# STM32.net
KiCad netlist of a schematic drawn in Altium Designer
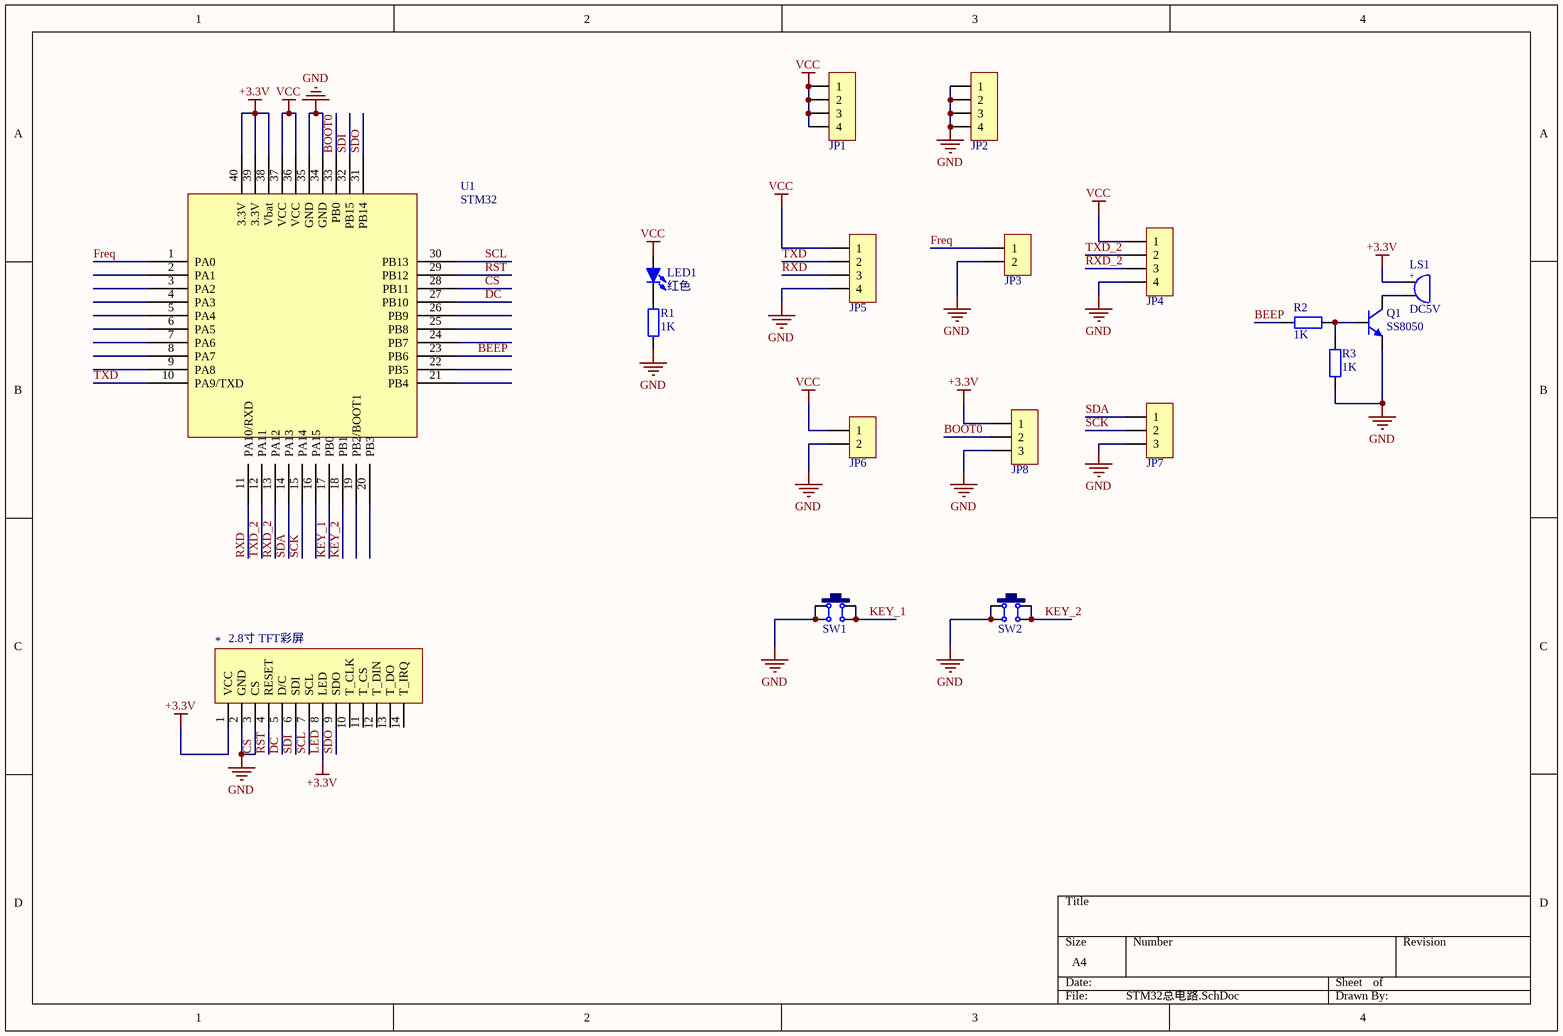
[diagram p0: STM32总电路.SchDoc]

(export (version "E")
  (design (tool "Eeschema 10.0.6"))
  (components
    (comp (ref "*")
      (value "2.8寸 TFT彩屏")
      (footprint "2.8寸TFT屏幕")
      (libsource (lib "altium-import") (part "root_0_2.8寸 TFT彩屏_"))
    )
    (comp (ref "JP1")
      (value "HDR-1X4")
      (footprint "HDR2.54-LI-4P")
      (description "4P接插件")
      (fields (field (name "版权归属") "源创客"))
      (libsource (lib "4.5   - 接插件-脚距2.54") (part "Header 4"))
    )
    (comp (ref "JP2")
      (value "HDR-1X4")
      (footprint "HDR2.54-LI-4P")
      (description "4P接插件")
      (fields (field (name "版权归属") "源创客"))
      (libsource (lib "4.5   - 接插件-脚距2.54") (part "Header 4"))
    )
    (comp (ref "JP3")
      (value "HDR-1X2")
      (footprint "XH2.54-LI-2P")
      (description "2P接插件")
      (fields (field (name "版权归属") "源创客"))
      (libsource (lib "4.5   - 接插件-脚距2.54") (part "Header 2"))
    )
    (comp (ref "JP4")
      (value "HDR-1X4")
      (footprint "XH2.54-LI-4P")
      (description "4P接插件")
      (fields (field (name "版权归属") "源创客"))
      (libsource (lib "4.5   - 接插件-脚距2.54") (part "Header 4"))
    )
    (comp (ref "JP5")
      (value "HDR-1X4")
      (footprint "XH2.54-LI-4P")
      (description "4P接插件")
      (fields (field (name "版权归属") "源创客"))
      (libsource (lib "4.5   - 接插件-脚距2.54") (part "Header 4"))
    )
    (comp (ref "JP6")
      (value "HDR-1X2")
      (footprint "XH2.54-LI-2P")
      (description "2P接插件")
      (fields (field (name "版权归属") "源创客"))
      (libsource (lib "4.5   - 接插件-脚距2.54") (part "Header 2"))
    )
    (comp (ref "JP7")
      (value "HDR-1X3")
      (footprint "HDR2.54-LI-3P")
      (description "3P接插件")
      (fields (field (name "版权归属") "源创客"))
      (libsource (lib "4.5   - 接插件-脚距2.54") (part "Header 3"))
    )
    (comp (ref "JP8")
      (value "HDR-1X3")
      (footprint "HDR2.54-LI-3P")
      (description "3P接插件")
      (fields (field (name "版权归属") "源创客"))
      (libsource (lib "4.5   - 接插件-脚距2.54") (part "Header 3"))
    )
    (comp (ref "LED1")
      (value "红色")
      (footprint "LED 5MM-B")
      (description "5mm插件LED")
      (fields (field (name "版权归属") "源创客"))
      (libsource (lib "altium-import") (part "root_0_LED-5MM_"))
    )
    (comp (ref "LS1")
      (value "DC5V")
      (footprint "BEEP 6.5x12x8.5")
      (description "蜂鸣器")
      (fields (field (name "版权归属") "源创客"))
      (libsource (lib "15.1 - 未分类器件") (part "BEEP"))
    )
    (comp (ref "Q1")
      (value "SS8050")
      (footprint "TO92A")
      (description "高频放大-NPN型")
      (fields (field (name "版权归属") "源创客"))
      (libsource (lib "6.2   - 三极管") (part "8050-DIP"))
    )
    (comp (ref "R1")
      (value "1K")
      (footprint "RS 1/4W")
      (description "直插色环电阻")
      (fields (field (name "版权归属") "源创客"))
      (libsource (lib "3.1   - 电阻-电容-电感") (part "R-CRR"))
    )
    (comp (ref "R2")
      (value "1K")
      (footprint "RS 1/4W")
      (description "直插色环电阻")
      (fields (field (name "版权归属") "源创客"))
      (libsource (lib "3.1   - 电阻-电容-电感") (part "R-CRR"))
    )
    (comp (ref "R3")
      (value "1K")
      (footprint "RS 1/4W")
      (description "直插色环电阻")
      (fields (field (name "版权归属") "源创客"))
      (libsource (lib "3.1   - 电阻-电容-电感") (part "R-CRR"))
    )
    (comp (ref "SW1")
      (value "6x6x5")
      (footprint "TSW DIP-6*6*6")
      (description "直插6x6轻触开关")
      (fields (field (name "版权归属") "源创客"))
      (libsource (lib "5.1   - 按键-开关") (part "TSW DIP-6x6"))
    )
    (comp (ref "SW2")
      (value "6x6x5")
      (footprint "TSW DIP-6*6*6")
      (description "直插6x6轻触开关")
      (fields (field (name "版权归属") "源创客"))
      (libsource (lib "5.1   - 按键-开关") (part "TSW DIP-6x6"))
    )
    (comp (ref "U1")
      (value "STM32")
      (footprint "STM32自制最小系统")
      (description "STM32最小系统自制")
      (libsource (lib "封装") (part "STM32最小系统"))
    )
  )
  (nets
    (net (code "1") (name "+3.3V") (class "Default")
      (node (ref "*") (pin "1") (pinfunction "VCC_1") (pintype "passive"))
      (node (ref "*") (pin "8") (pinfunction "LED_8") (pintype "passive"))
      (node (ref "JP8") (pin "1") (pinfunction "1_1") (pintype "passive"))
      (node (ref "LS1") (pin "1") (pinfunction "1_1") (pintype "passive"))
      (node (ref "U1") (pin "38") (pinfunction "Vbat_38") (pintype "passive"))
      (node (ref "U1") (pin "39") (pinfunction "3.3V_39") (pintype "passive"))
      (node (ref "U1") (pin "40") (pinfunction "3.3V_40") (pintype "passive"))
    )
    (net (code "2") (name "/BEEP") (class "Default")
      (node (ref "R2") (pin "1") (pinfunction "1_1") (pintype "passive"))
      (node (ref "U1") (pin "23") (pinfunction "PB6_23") (pintype "passive"))
    )
    (net (code "3") (name "/BOOT0") (class "Default")
      (node (ref "JP8") (pin "2") (pinfunction "2_2") (pintype "passive"))
      (node (ref "U1") (pin "33") (pinfunction "PB0_33") (pintype "passive"))
    )
    (net (code "4") (name "/DC") (class "Default")
      (node (ref "*") (pin "5") (pinfunction "D/C_5") (pintype "passive"))
      (node (ref "U1") (pin "27") (pinfunction "PB10_27") (pintype "passive"))
    )
    (net (code "5") (name "/Freq") (class "Default")
      (node (ref "JP3") (pin "1") (pinfunction "1_1") (pintype "passive"))
      (node (ref "U1") (pin "1") (pinfunction "PA0_1") (pintype "passive"))
    )
    (net (code "6") (name "/KEY_1") (class "Default")
      (node (ref "SW1") (pin "2") (pinfunction "2_2") (pintype "passive"))
      (node (ref "SW1") (pin "3") (pinfunction "3_3") (pintype "passive"))
      (node (ref "U1") (pin "17") (pinfunction "PB0_17") (pintype "passive"))
    )
    (net (code "7") (name "/KEY_2") (class "Default")
      (node (ref "SW2") (pin "2") (pinfunction "2_2") (pintype "passive"))
      (node (ref "SW2") (pin "3") (pinfunction "3_3") (pintype "passive"))
      (node (ref "U1") (pin "18") (pinfunction "PB1_18") (pintype "passive"))
    )
    (net (code "8") (name "/RST") (class "Default")
      (node (ref "*") (pin "4") (pinfunction "RESET_4") (pintype "passive"))
      (node (ref "U1") (pin "29") (pinfunction "PB12_29") (pintype "passive"))
    )
    (net (code "9") (name "/RXD") (class "Default")
      (node (ref "JP5") (pin "3") (pinfunction "3_3") (pintype "passive"))
      (node (ref "U1") (pin "11") (pinfunction "PA10/RXD_11") (pintype "passive"))
    )
    (net (code "10") (name "/RXD_2") (class "Default")
      (node (ref "JP4") (pin "3") (pinfunction "3_3") (pintype "passive"))
      (node (ref "U1") (pin "13") (pinfunction "PA12_13") (pintype "passive"))
    )
    (net (code "11") (name "/SCK") (class "Default")
      (node (ref "JP7") (pin "2") (pinfunction "2_2") (pintype "passive"))
      (node (ref "U1") (pin "15") (pinfunction "PA14_15") (pintype "passive"))
    )
    (net (code "12") (name "/SCL") (class "Default")
      (node (ref "*") (pin "7") (pinfunction "SCL_7") (pintype "passive"))
      (node (ref "U1") (pin "30") (pinfunction "PB13_30") (pintype "passive"))
    )
    (net (code "13") (name "/SDA") (class "Default")
      (node (ref "JP7") (pin "1") (pinfunction "1_1") (pintype "passive"))
      (node (ref "U1") (pin "14") (pinfunction "PA13_14") (pintype "passive"))
    )
    (net (code "14") (name "/SDI") (class "Default")
      (node (ref "*") (pin "6") (pinfunction "SDI_6") (pintype "passive"))
      (node (ref "U1") (pin "32") (pinfunction "PB15_32") (pintype "passive"))
    )
    (net (code "15") (name "/SDO") (class "Default")
      (node (ref "*") (pin "9") (pinfunction "SDO_9") (pintype "passive"))
      (node (ref "U1") (pin "31") (pinfunction "PB14_31") (pintype "passive"))
    )
    (net (code "16") (name "/TXD") (class "Default")
      (node (ref "JP5") (pin "2") (pinfunction "2_2") (pintype "passive"))
      (node (ref "U1") (pin "10") (pinfunction "PA9/TXD_10") (pintype "passive"))
    )
    (net (code "17") (name "/TXD_2") (class "Default")
      (node (ref "JP4") (pin "2") (pinfunction "2_2") (pintype "passive"))
      (node (ref "U1") (pin "12") (pinfunction "PA11_12") (pintype "passive"))
    )
    (net (code "18") (name "GND") (class "Default")
      (node (ref "*") (pin "2") (pinfunction "GND_2") (pintype "passive"))
      (node (ref "*") (pin "3") (pinfunction "CS_3") (pintype "passive"))
      (node (ref "JP2") (pin "1") (pinfunction "1_1") (pintype "passive"))
      (node (ref "JP2") (pin "2") (pinfunction "2_2") (pintype "passive"))
      (node (ref "JP2") (pin "3") (pinfunction "3_3") (pintype "passive"))
      (node (ref "JP2") (pin "4") (pinfunction "4_4") (pintype "passive"))
      (node (ref "JP3") (pin "2") (pinfunction "2_2") (pintype "passive"))
      (node (ref "JP4") (pin "4") (pinfunction "4_4") (pintype "passive"))
      (node (ref "JP5") (pin "4") (pinfunction "4_4") (pintype "passive"))
      (node (ref "JP6") (pin "2") (pinfunction "2_2") (pintype "passive"))
      (node (ref "JP7") (pin "3") (pinfunction "3_3") (pintype "passive"))
      (node (ref "JP8") (pin "3") (pinfunction "3_3") (pintype "passive"))
      (node (ref "Q1") (pin "1") (pinfunction "E_1") (pintype "passive"))
      (node (ref "R1") (pin "1") (pinfunction "1_1") (pintype "passive"))
      (node (ref "R3") (pin "1") (pinfunction "1_1") (pintype "passive"))
      (node (ref "SW1") (pin "1") (pinfunction "1_1") (pintype "passive"))
      (node (ref "SW1") (pin "4") (pinfunction "4_4") (pintype "passive"))
      (node (ref "SW2") (pin "1") (pinfunction "1_1") (pintype "passive"))
      (node (ref "SW2") (pin "4") (pinfunction "4_4") (pintype "passive"))
      (node (ref "U1") (pin "28") (pinfunction "PB11_28") (pintype "passive"))
      (node (ref "U1") (pin "34") (pinfunction "GND_34") (pintype "passive"))
      (node (ref "U1") (pin "35") (pinfunction "GND_35") (pintype "passive"))
    )
    (net (code "19") (name "Net-(LED1-K)") (class "Default")
      (node (ref "LED1") (pin "2") (pinfunction "K_2") (pintype "passive"))
      (node (ref "R1") (pin "2") (pinfunction "2_2") (pintype "passive"))
    )
    (net (code "20") (name "Net-(Q1-B)") (class "Default")
      (node (ref "Q1") (pin "2") (pinfunction "B_2") (pintype "passive"))
      (node (ref "R2") (pin "2") (pinfunction "2_2") (pintype "passive"))
      (node (ref "R3") (pin "2") (pinfunction "2_2") (pintype "passive"))
    )
    (net (code "21") (name "Net-(Q1-C)") (class "Default")
      (node (ref "LS1") (pin "2") (pinfunction "2_2") (pintype "passive"))
      (node (ref "Q1") (pin "3") (pinfunction "C_3") (pintype "passive"))
    )
    (net (code "22") (name "VCC") (class "Default")
      (node (ref "JP1") (pin "1") (pinfunction "1_1") (pintype "passive"))
      (node (ref "JP1") (pin "2") (pinfunction "2_2") (pintype "passive"))
      (node (ref "JP1") (pin "3") (pinfunction "3_3") (pintype "passive"))
      (node (ref "JP1") (pin "4") (pinfunction "4_4") (pintype "passive"))
      (node (ref "JP4") (pin "1") (pinfunction "1_1") (pintype "passive"))
      (node (ref "JP5") (pin "1") (pinfunction "1_1") (pintype "passive"))
      (node (ref "JP6") (pin "1") (pinfunction "1_1") (pintype "passive"))
      (node (ref "LED1") (pin "1") (pinfunction "A_1") (pintype "passive"))
      (node (ref "U1") (pin "36") (pinfunction "VCC_36") (pintype "passive"))
      (node (ref "U1") (pin "37") (pinfunction "VCC_37") (pintype "passive"))
    )
    (net (code "23") (name "unconnected-(*-T_CLK-Pad10)") (class "Default")
      (node (ref "*") (pin "10") (pinfunction "T_CLK_10") (pintype "passive"))
    )
    (net (code "24") (name "unconnected-(*-T_CS-Pad11)") (class "Default")
      (node (ref "*") (pin "11") (pinfunction "T_CS_11") (pintype "passive"))
    )
    (net (code "25") (name "unconnected-(*-T_DIN-Pad12)") (class "Default")
      (node (ref "*") (pin "12") (pinfunction "T_DIN_12") (pintype "passive"))
    )
    (net (code "26") (name "unconnected-(*-T_DO-Pad13)") (class "Default")
      (node (ref "*") (pin "13") (pinfunction "T_DO_13") (pintype "passive"))
    )
    (net (code "27") (name "unconnected-(*-T_IRQ-Pad14)") (class "Default")
      (node (ref "*") (pin "14") (pinfunction "T_IRQ_14") (pintype "passive"))
    )
    (net (code "28") (name "unconnected-(U1-PA1-Pad2)") (class "Default")
      (node (ref "U1") (pin "2") (pinfunction "PA1_2") (pintype "passive"))
    )
    (net (code "29") (name "unconnected-(U1-PA2-Pad3)") (class "Default")
      (node (ref "U1") (pin "3") (pinfunction "PA2_3") (pintype "passive"))
    )
    (net (code "30") (name "unconnected-(U1-PA3-Pad4)") (class "Default")
      (node (ref "U1") (pin "4") (pinfunction "PA3_4") (pintype "passive"))
    )
    (net (code "31") (name "unconnected-(U1-PA4-Pad5)") (class "Default")
      (node (ref "U1") (pin "5") (pinfunction "PA4_5") (pintype "passive"))
    )
    (net (code "32") (name "unconnected-(U1-PA5-Pad6)") (class "Default")
      (node (ref "U1") (pin "6") (pinfunction "PA5_6") (pintype "passive"))
    )
    (net (code "33") (name "unconnected-(U1-PA6-Pad7)") (class "Default")
      (node (ref "U1") (pin "7") (pinfunction "PA6_7") (pintype "passive"))
    )
    (net (code "34") (name "unconnected-(U1-PA7-Pad8)") (class "Default")
      (node (ref "U1") (pin "8") (pinfunction "PA7_8") (pintype "passive"))
    )
    (net (code "35") (name "unconnected-(U1-PA8-Pad9)") (class "Default")
      (node (ref "U1") (pin "9") (pinfunction "PA8_9") (pintype "passive"))
    )
    (net (code "36") (name "unconnected-(U1-PA15-Pad16)") (class "Default")
      (node (ref "U1") (pin "16") (pinfunction "PA15_16") (pintype "passive"))
    )
    (net (code "37") (name "unconnected-(U1-PB2{slash}BOOT1-Pad19)") (class "Default")
      (node (ref "U1") (pin "19") (pinfunction "PB2/BOOT1_19") (pintype "passive"))
    )
    (net (code "38") (name "unconnected-(U1-PB3-Pad20)") (class "Default")
      (node (ref "U1") (pin "20") (pinfunction "PB3_20") (pintype "passive"))
    )
    (net (code "39") (name "unconnected-(U1-PB4-Pad21)") (class "Default")
      (node (ref "U1") (pin "21") (pinfunction "PB4_21") (pintype "passive"))
    )
    (net (code "40") (name "unconnected-(U1-PB5-Pad22)") (class "Default")
      (node (ref "U1") (pin "22") (pinfunction "PB5_22") (pintype "passive"))
    )
    (net (code "41") (name "unconnected-(U1-PB7-Pad24)") (class "Default")
      (node (ref "U1") (pin "24") (pinfunction "PB7_24") (pintype "passive"))
    )
    (net (code "42") (name "unconnected-(U1-PB8-Pad25)") (class "Default")
      (node (ref "U1") (pin "25") (pinfunction "PB8_25") (pintype "passive"))
    )
    (net (code "43") (name "unconnected-(U1-PB9-Pad26)") (class "Default")
      (node (ref "U1") (pin "26") (pinfunction "PB9_26") (pintype "passive"))
    )
  )
)
